# Connector.net
KiCad netlist of a schematic drawn in Altium Designer
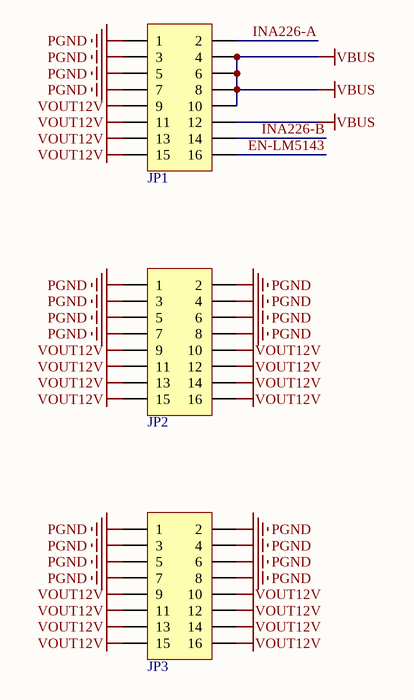
[diagram p0: Connector.SchDoc]

(export (version "E")
  (design (tool "Eeschema 10.0.6"))
  (components
    (comp (ref "JP1")
      (value "Header 8X2")
      (footprint "HDR2.54-LI-2x8P")
      (description "8*2P接插件")
      (fields (field (name "版权归属") "源创客"))
      (libsource (lib "Connector-PinHeader") (part "Header 8X2"))
    )
    (comp (ref "JP2")
      (value "Header 8X2")
      (footprint "HDR2.54-LI-2x8P")
      (description "8*2P接插件")
      (fields (field (name "版权归属") "源创客"))
      (libsource (lib "Connector-PinHeader") (part "Header 8X2"))
    )
    (comp (ref "JP3")
      (value "Header 8X2")
      (footprint "HDR2.54-LI-2x8P")
      (description "8*2P接插件")
      (fields (field (name "版权归属") "源创客"))
      (libsource (lib "Connector-PinHeader") (part "Header 8X2"))
    )
  )
  (nets
    (net (code "1") (name "/EN-LM5143") (class "Default")
      (node (ref "JP1") (pin "16") (pinfunction "16_16") (pintype "passive"))
    )
    (net (code "2") (name "/INA226-A") (class "Default")
      (node (ref "JP1") (pin "2") (pinfunction "2_2") (pintype "passive"))
    )
    (net (code "3") (name "/INA226-B") (class "Default")
      (node (ref "JP1") (pin "14") (pinfunction "14_14") (pintype "passive"))
    )
    (net (code "4") (name "PGND") (class "Default")
      (node (ref "JP1") (pin "1") (pinfunction "1_1") (pintype "passive"))
      (node (ref "JP1") (pin "3") (pinfunction "3_3") (pintype "passive"))
      (node (ref "JP1") (pin "5") (pinfunction "5_5") (pintype "passive"))
      (node (ref "JP1") (pin "7") (pinfunction "7_7") (pintype "passive"))
      (node (ref "JP2") (pin "1") (pinfunction "1_1") (pintype "passive"))
      (node (ref "JP2") (pin "2") (pinfunction "2_2") (pintype "passive"))
      (node (ref "JP2") (pin "3") (pinfunction "3_3") (pintype "passive"))
      (node (ref "JP2") (pin "4") (pinfunction "4_4") (pintype "passive"))
      (node (ref "JP2") (pin "5") (pinfunction "5_5") (pintype "passive"))
      (node (ref "JP2") (pin "6") (pinfunction "6_6") (pintype "passive"))
      (node (ref "JP2") (pin "7") (pinfunction "7_7") (pintype "passive"))
      (node (ref "JP2") (pin "8") (pinfunction "8_8") (pintype "passive"))
      (node (ref "JP3") (pin "1") (pinfunction "1_1") (pintype "passive"))
      (node (ref "JP3") (pin "2") (pinfunction "2_2") (pintype "passive"))
      (node (ref "JP3") (pin "3") (pinfunction "3_3") (pintype "passive"))
      (node (ref "JP3") (pin "4") (pinfunction "4_4") (pintype "passive"))
      (node (ref "JP3") (pin "5") (pinfunction "5_5") (pintype "passive"))
      (node (ref "JP3") (pin "6") (pinfunction "6_6") (pintype "passive"))
      (node (ref "JP3") (pin "7") (pinfunction "7_7") (pintype "passive"))
      (node (ref "JP3") (pin "8") (pinfunction "8_8") (pintype "passive"))
    )
    (net (code "5") (name "VBUS") (class "Default")
      (node (ref "JP1") (pin "10") (pinfunction "10_10") (pintype "passive"))
      (node (ref "JP1") (pin "12") (pinfunction "12_12") (pintype "passive"))
      (node (ref "JP1") (pin "4") (pinfunction "4_4") (pintype "passive"))
      (node (ref "JP1") (pin "6") (pinfunction "6_6") (pintype "passive"))
      (node (ref "JP1") (pin "8") (pinfunction "8_8") (pintype "passive"))
    )
    (net (code "6") (name "VOUT12V") (class "Default")
      (node (ref "JP1") (pin "11") (pinfunction "11_11") (pintype "passive"))
      (node (ref "JP1") (pin "13") (pinfunction "13_13") (pintype "passive"))
      (node (ref "JP1") (pin "15") (pinfunction "15_15") (pintype "passive"))
      (node (ref "JP1") (pin "9") (pinfunction "9_9") (pintype "passive"))
      (node (ref "JP2") (pin "10") (pinfunction "10_10") (pintype "passive"))
      (node (ref "JP2") (pin "11") (pinfunction "11_11") (pintype "passive"))
      (node (ref "JP2") (pin "12") (pinfunction "12_12") (pintype "passive"))
      (node (ref "JP2") (pin "13") (pinfunction "13_13") (pintype "passive"))
      (node (ref "JP2") (pin "14") (pinfunction "14_14") (pintype "passive"))
      (node (ref "JP2") (pin "15") (pinfunction "15_15") (pintype "passive"))
      (node (ref "JP2") (pin "16") (pinfunction "16_16") (pintype "passive"))
      (node (ref "JP2") (pin "9") (pinfunction "9_9") (pintype "passive"))
      (node (ref "JP3") (pin "10") (pinfunction "10_10") (pintype "passive"))
      (node (ref "JP3") (pin "11") (pinfunction "11_11") (pintype "passive"))
      (node (ref "JP3") (pin "12") (pinfunction "12_12") (pintype "passive"))
      (node (ref "JP3") (pin "13") (pinfunction "13_13") (pintype "passive"))
      (node (ref "JP3") (pin "14") (pinfunction "14_14") (pintype "passive"))
      (node (ref "JP3") (pin "15") (pinfunction "15_15") (pintype "passive"))
      (node (ref "JP3") (pin "16") (pinfunction "16_16") (pintype "passive"))
      (node (ref "JP3") (pin "9") (pinfunction "9_9") (pintype "passive"))
    )
  )
)
